# TQFP-32_to_DIP-32.net
KiCad netlist of a schematic drawn in EAGLE
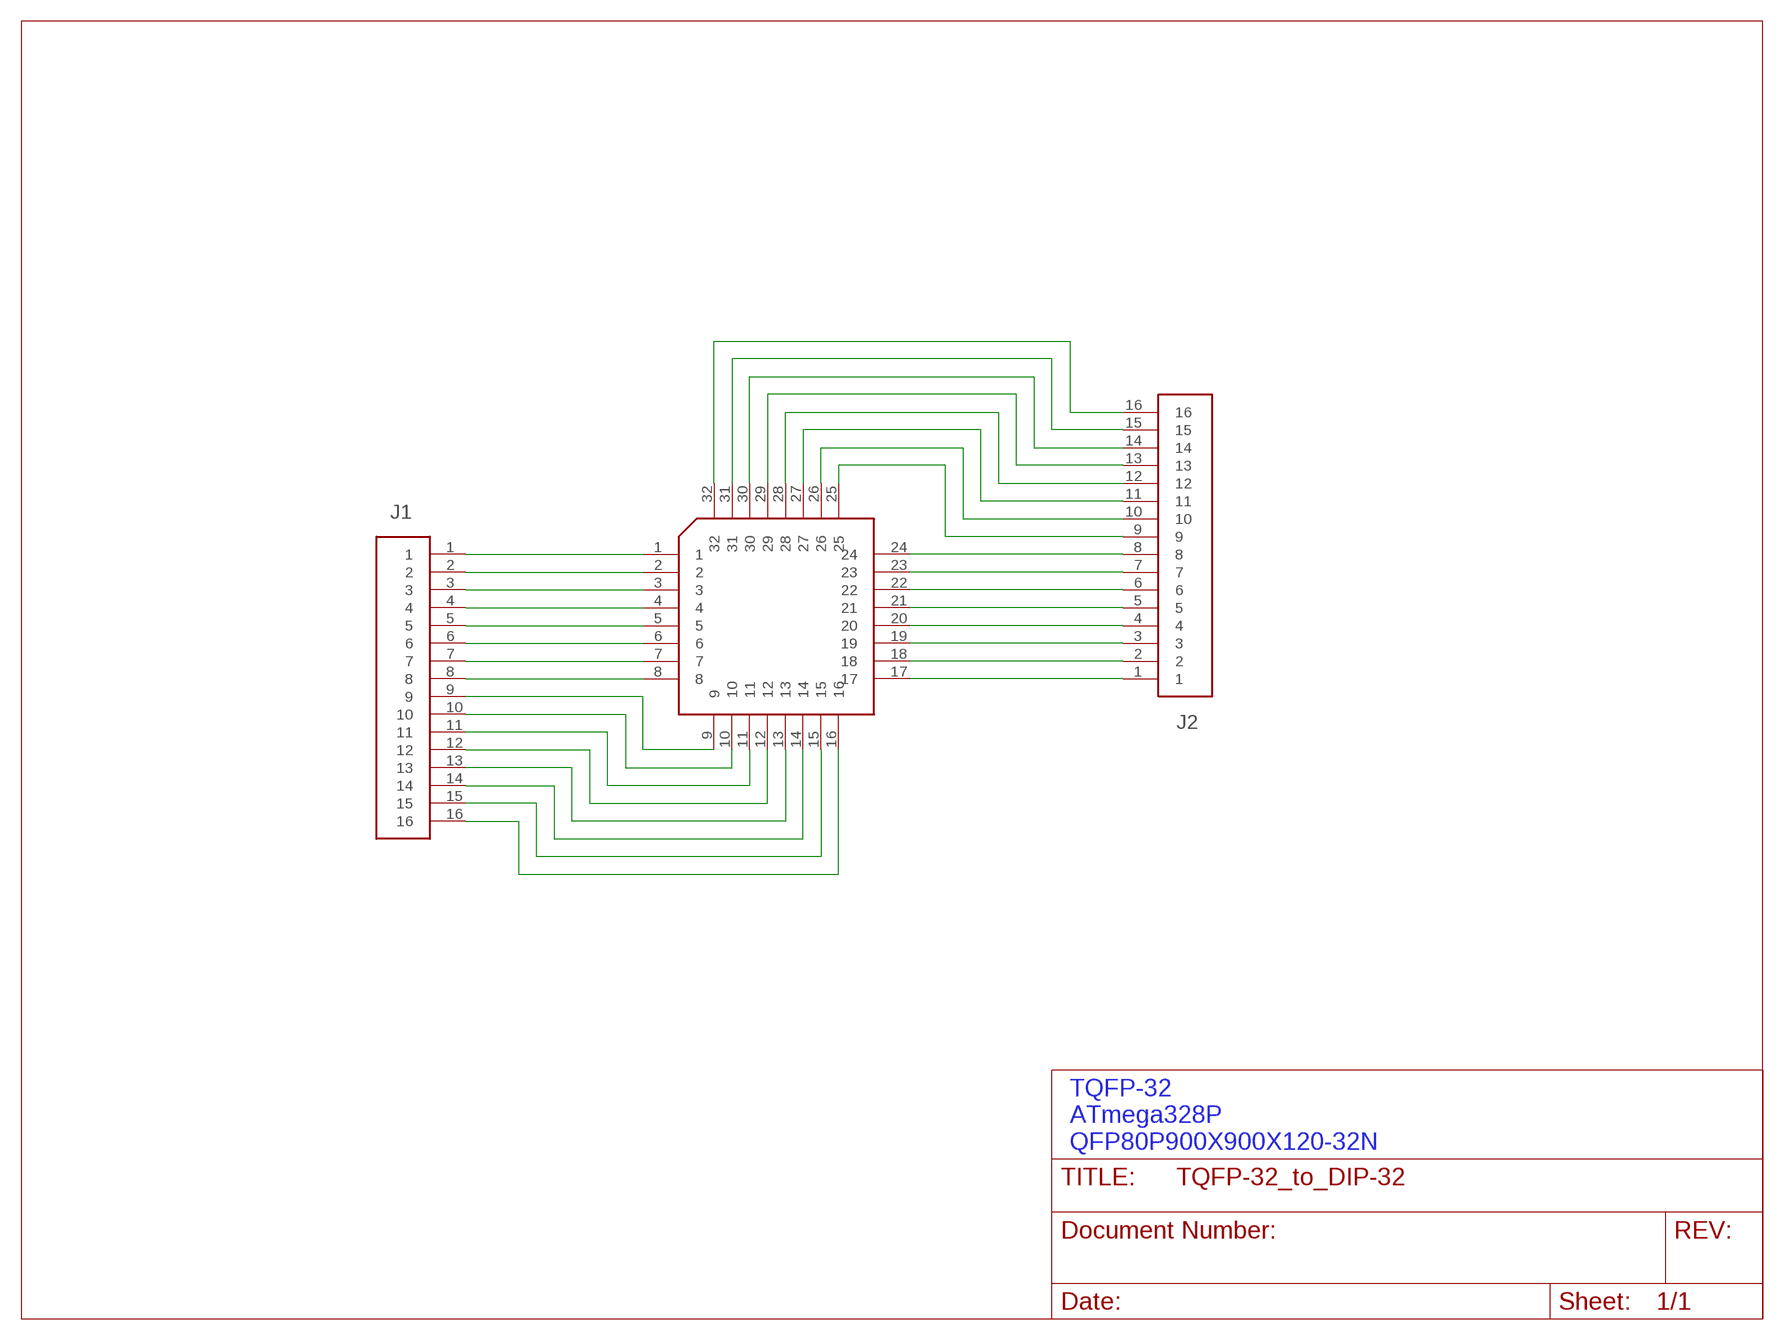
[diagram p0: schematic, sheet 1]

(export (version "E")
  (design (tool "Eeschema 10.0.6"))
  (components
    (comp (ref "J1")
      (value "CONNECTOR_16")
      (footprint "eagle-import:68000-116HLF")
      (libsource (lib "eagle-import") (part "CONNECTOR_16"))
    )
    (comp (ref "J2")
      (value "CONNECTOR_16-NO_SQUARE")
      (footprint "eagle-import:68000-116HLF-NO-SQUARE")
      (libsource (lib "eagle-import") (part "CONNECTOR_16-NO_SQUARE"))
    )
    (comp (ref "U1")
      (value "IC-GENERIC-TQFP-32")
      (footprint "eagle-import:QFP80P900X900X120-32N")
      (libsource (lib "eagle-import") (part "IC-GENERIC-TQFP-32"))
    )
  )
  (nets
    (net (code "1") (name "Net-(J1-Pad1)") (class "Default")
      (node (ref "J1") (pin "1") (pinfunction "1_1") (pintype "bidirectional"))
      (node (ref "U1") (pin "1") (pinfunction "1_1") (pintype "bidirectional"))
    )
    (net (code "2") (name "Net-(J1-Pad2)") (class "Default")
      (node (ref "J1") (pin "2") (pinfunction "2_2") (pintype "bidirectional"))
      (node (ref "U1") (pin "2") (pinfunction "2_2") (pintype "bidirectional"))
    )
    (net (code "3") (name "Net-(J1-Pad3)") (class "Default")
      (node (ref "J1") (pin "3") (pinfunction "3_3") (pintype "bidirectional"))
      (node (ref "U1") (pin "3") (pinfunction "3_3") (pintype "bidirectional"))
    )
    (net (code "4") (name "Net-(J1-Pad4)") (class "Default")
      (node (ref "J1") (pin "4") (pinfunction "4_4") (pintype "bidirectional"))
      (node (ref "U1") (pin "4") (pinfunction "4_4") (pintype "bidirectional"))
    )
    (net (code "5") (name "Net-(J1-Pad5)") (class "Default")
      (node (ref "J1") (pin "5") (pinfunction "5_5") (pintype "bidirectional"))
      (node (ref "U1") (pin "5") (pinfunction "5_5") (pintype "bidirectional"))
    )
    (net (code "6") (name "Net-(J1-Pad6)") (class "Default")
      (node (ref "J1") (pin "6") (pinfunction "6_6") (pintype "bidirectional"))
      (node (ref "U1") (pin "6") (pinfunction "6_6") (pintype "bidirectional"))
    )
    (net (code "7") (name "Net-(J1-Pad7)") (class "Default")
      (node (ref "J1") (pin "7") (pinfunction "7_7") (pintype "bidirectional"))
      (node (ref "U1") (pin "7") (pinfunction "7_7") (pintype "bidirectional"))
    )
    (net (code "8") (name "Net-(J1-Pad8)") (class "Default")
      (node (ref "J1") (pin "8") (pinfunction "8_8") (pintype "bidirectional"))
      (node (ref "U1") (pin "8") (pinfunction "8_8") (pintype "bidirectional"))
    )
    (net (code "9") (name "Net-(J1-Pad9)") (class "Default")
      (node (ref "J1") (pin "9") (pinfunction "9_9") (pintype "bidirectional"))
      (node (ref "U1") (pin "9") (pinfunction "9_9") (pintype "bidirectional"))
    )
    (net (code "10") (name "Net-(J1-Pad10)") (class "Default")
      (node (ref "J1") (pin "10") (pinfunction "10_10") (pintype "bidirectional"))
      (node (ref "U1") (pin "10") (pinfunction "10_10") (pintype "bidirectional"))
    )
    (net (code "11") (name "Net-(J1-Pad11)") (class "Default")
      (node (ref "J1") (pin "11") (pinfunction "11_11") (pintype "bidirectional"))
      (node (ref "U1") (pin "11") (pinfunction "11_11") (pintype "bidirectional"))
    )
    (net (code "12") (name "Net-(J1-Pad12)") (class "Default")
      (node (ref "J1") (pin "12") (pinfunction "12_12") (pintype "bidirectional"))
      (node (ref "U1") (pin "12") (pinfunction "12_12") (pintype "bidirectional"))
    )
    (net (code "13") (name "Net-(J1-Pad13)") (class "Default")
      (node (ref "J1") (pin "13") (pinfunction "13_13") (pintype "bidirectional"))
      (node (ref "U1") (pin "13") (pinfunction "13_13") (pintype "bidirectional"))
    )
    (net (code "14") (name "Net-(J1-Pad14)") (class "Default")
      (node (ref "J1") (pin "14") (pinfunction "14_14") (pintype "bidirectional"))
      (node (ref "U1") (pin "14") (pinfunction "14_14") (pintype "bidirectional"))
    )
    (net (code "15") (name "Net-(J1-Pad15)") (class "Default")
      (node (ref "J1") (pin "15") (pinfunction "15_15") (pintype "bidirectional"))
      (node (ref "U1") (pin "15") (pinfunction "15_15") (pintype "bidirectional"))
    )
    (net (code "16") (name "Net-(J1-Pad16)") (class "Default")
      (node (ref "J1") (pin "16") (pinfunction "16_16") (pintype "bidirectional"))
      (node (ref "U1") (pin "16") (pinfunction "16_16") (pintype "bidirectional"))
    )
    (net (code "17") (name "Net-(J2-Pad1)") (class "Default")
      (node (ref "J2") (pin "1") (pinfunction "1_1") (pintype "bidirectional"))
      (node (ref "U1") (pin "17") (pinfunction "17_17") (pintype "bidirectional"))
    )
    (net (code "18") (name "Net-(J2-Pad2)") (class "Default")
      (node (ref "J2") (pin "2") (pinfunction "2_2") (pintype "bidirectional"))
      (node (ref "U1") (pin "18") (pinfunction "18_18") (pintype "bidirectional"))
    )
    (net (code "19") (name "Net-(J2-Pad3)") (class "Default")
      (node (ref "J2") (pin "3") (pinfunction "3_3") (pintype "bidirectional"))
      (node (ref "U1") (pin "19") (pinfunction "19_19") (pintype "bidirectional"))
    )
    (net (code "20") (name "Net-(J2-Pad4)") (class "Default")
      (node (ref "J2") (pin "4") (pinfunction "4_4") (pintype "bidirectional"))
      (node (ref "U1") (pin "20") (pinfunction "20_20") (pintype "bidirectional"))
    )
    (net (code "21") (name "Net-(J2-Pad5)") (class "Default")
      (node (ref "J2") (pin "5") (pinfunction "5_5") (pintype "bidirectional"))
      (node (ref "U1") (pin "21") (pinfunction "21_21") (pintype "bidirectional"))
    )
    (net (code "22") (name "Net-(J2-Pad6)") (class "Default")
      (node (ref "J2") (pin "6") (pinfunction "6_6") (pintype "bidirectional"))
      (node (ref "U1") (pin "22") (pinfunction "22_22") (pintype "bidirectional"))
    )
    (net (code "23") (name "Net-(J2-Pad7)") (class "Default")
      (node (ref "J2") (pin "7") (pinfunction "7_7") (pintype "bidirectional"))
      (node (ref "U1") (pin "23") (pinfunction "23_23") (pintype "bidirectional"))
    )
    (net (code "24") (name "Net-(J2-Pad8)") (class "Default")
      (node (ref "J2") (pin "8") (pinfunction "8_8") (pintype "bidirectional"))
      (node (ref "U1") (pin "24") (pinfunction "24_24") (pintype "bidirectional"))
    )
    (net (code "25") (name "Net-(J2-Pad9)") (class "Default")
      (node (ref "J2") (pin "9") (pinfunction "9_9") (pintype "bidirectional"))
      (node (ref "U1") (pin "25") (pinfunction "25_25") (pintype "bidirectional"))
    )
    (net (code "26") (name "Net-(J2-Pad10)") (class "Default")
      (node (ref "J2") (pin "10") (pinfunction "10_10") (pintype "bidirectional"))
      (node (ref "U1") (pin "26") (pinfunction "26_26") (pintype "bidirectional"))
    )
    (net (code "27") (name "Net-(J2-Pad11)") (class "Default")
      (node (ref "J2") (pin "11") (pinfunction "11_11") (pintype "bidirectional"))
      (node (ref "U1") (pin "27") (pinfunction "27_27") (pintype "bidirectional"))
    )
    (net (code "28") (name "Net-(J2-Pad12)") (class "Default")
      (node (ref "J2") (pin "12") (pinfunction "12_12") (pintype "bidirectional"))
      (node (ref "U1") (pin "28") (pinfunction "28_28") (pintype "bidirectional"))
    )
    (net (code "29") (name "Net-(J2-Pad13)") (class "Default")
      (node (ref "J2") (pin "13") (pinfunction "13_13") (pintype "bidirectional"))
      (node (ref "U1") (pin "29") (pinfunction "29_29") (pintype "bidirectional"))
    )
    (net (code "30") (name "Net-(J2-Pad14)") (class "Default")
      (node (ref "J2") (pin "14") (pinfunction "14_14") (pintype "bidirectional"))
      (node (ref "U1") (pin "30") (pinfunction "30_30") (pintype "bidirectional"))
    )
    (net (code "31") (name "Net-(J2-Pad15)") (class "Default")
      (node (ref "J2") (pin "15") (pinfunction "15_15") (pintype "bidirectional"))
      (node (ref "U1") (pin "31") (pinfunction "31_31") (pintype "bidirectional"))
    )
    (net (code "32") (name "Net-(J2-Pad16)") (class "Default")
      (node (ref "J2") (pin "16") (pinfunction "16_16") (pintype "bidirectional"))
      (node (ref "U1") (pin "32") (pinfunction "32_32") (pintype "bidirectional"))
    )
  )
)
